# INTERFACE.net
KiCad netlist of a schematic drawn in Altium Designer
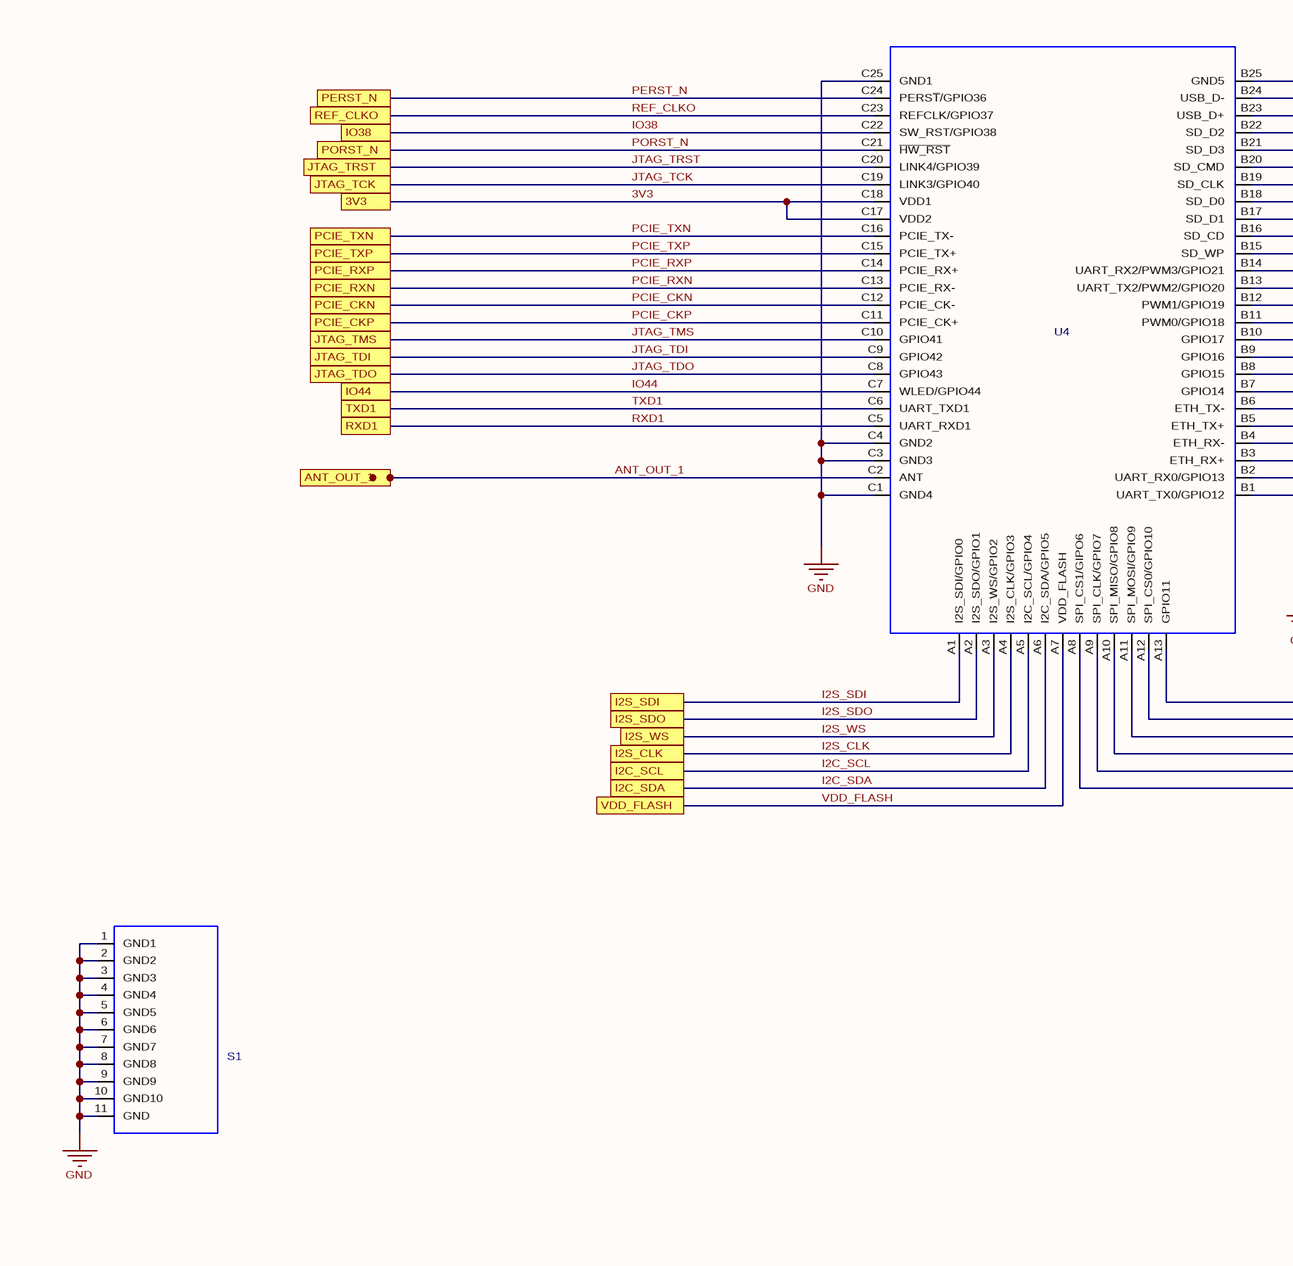
[diagram p0: INTERFACE.SchDoc, left]
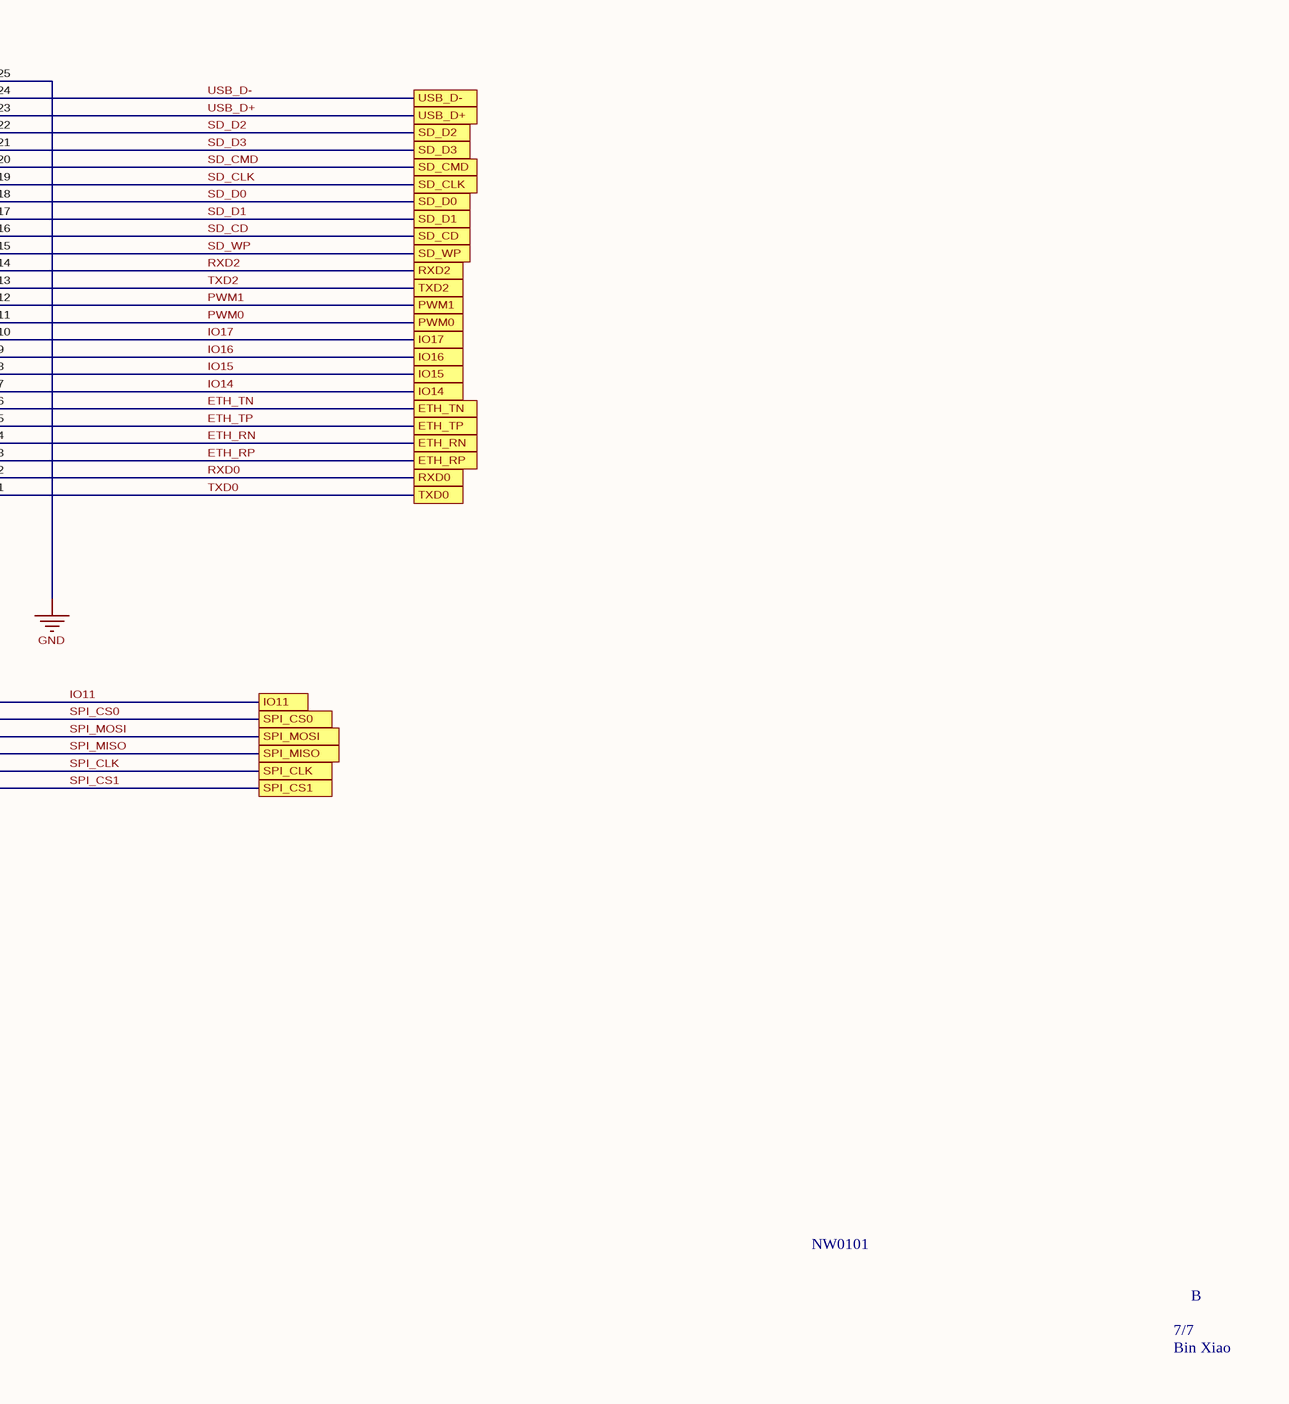
[diagram p1: INTERFACE.SchDoc, right]

(export (version "E")
  (design (tool "Eeschema 10.0.6"))
  (components
    (comp (ref "S1")
      (value "O2S-SHIELD")
      (footprint "O2S-SHIELD")
      (description "O2S SHIELD")
      (fields (field (name "MANUFACTURER") "RYSE Inc."))
      (libsource (lib "*") (part "O2S-SHIELD"))
    )
    (comp (ref "U4")
      (value "OMEGA2S-PCB")
      (footprint "OMEGA2S+PCB")
      (description "RX TXRX MODULE WIFI U.FL SMD")
      (fields (field (name "MANUFACTURER") "Onion Corporation") (field (name "PART NUMBER") "OM-O2S"))
      (libsource (lib "*") (part "OMEGA2S-PCB"))
    )
  )
  (nets
    (net (code "1") (name "/3V3") (class "Default")
      (node (ref "U4") (pin "C17") (pinfunction "VDD2_C17") (pintype "passive"))
      (node (ref "U4") (pin "C18") (pinfunction "VDD1_C18") (pintype "passive"))
    )
    (net (code "2") (name "/ANT_OUT_1") (class "Default")
      (node (ref "U4") (pin "C2") (pinfunction "ANT_C2") (pintype "passive"))
    )
    (net (code "3") (name "/ETH_RN") (class "Default")
      (node (ref "U4") (pin "B4") (pinfunction "ETH_RX-_B4") (pintype "passive"))
    )
    (net (code "4") (name "/ETH_RP") (class "Default")
      (node (ref "U4") (pin "B3") (pinfunction "ETH_RX+_B3") (pintype "passive"))
    )
    (net (code "5") (name "/ETH_TN") (class "Default")
      (node (ref "U4") (pin "B6") (pinfunction "ETH_TX-_B6") (pintype "passive"))
    )
    (net (code "6") (name "/ETH_TP") (class "Default")
      (node (ref "U4") (pin "B5") (pinfunction "ETH_TX+_B5") (pintype "passive"))
    )
    (net (code "7") (name "/I2C_SCL") (class "Default")
      (node (ref "U4") (pin "A5") (pinfunction "I2C_SCL/GPIO4_A5") (pintype "passive"))
    )
    (net (code "8") (name "/I2C_SDA") (class "Default")
      (node (ref "U4") (pin "A6") (pinfunction "I2C_SDA/GPIO5_A6") (pintype "passive"))
    )
    (net (code "9") (name "/I2S_CLK") (class "Default")
      (node (ref "U4") (pin "A4") (pinfunction "I2S_CLK/GPIO3_A4") (pintype "passive"))
    )
    (net (code "10") (name "/I2S_SDI") (class "Default")
      (node (ref "U4") (pin "A1") (pinfunction "I2S_SDI/GPIO0_A1") (pintype "passive"))
    )
    (net (code "11") (name "/I2S_SDO") (class "Default")
      (node (ref "U4") (pin "A2") (pinfunction "I2S_SDO/GPIO1_A2") (pintype "passive"))
    )
    (net (code "12") (name "/I2S_WS") (class "Default")
      (node (ref "U4") (pin "A3") (pinfunction "I2S_WS/GPIO2_A3") (pintype "passive"))
    )
    (net (code "13") (name "/IO11") (class "Default")
      (node (ref "U4") (pin "A13") (pinfunction "GPIO11_A13") (pintype "passive"))
    )
    (net (code "14") (name "/IO14") (class "Default")
      (node (ref "U4") (pin "B7") (pinfunction "GPIO14_B7") (pintype "passive"))
    )
    (net (code "15") (name "/IO15") (class "Default")
      (node (ref "U4") (pin "B8") (pinfunction "GPIO15_B8") (pintype "passive"))
    )
    (net (code "16") (name "/IO16") (class "Default")
      (node (ref "U4") (pin "B9") (pinfunction "GPIO16_B9") (pintype "passive"))
    )
    (net (code "17") (name "/IO17") (class "Default")
      (node (ref "U4") (pin "B10") (pinfunction "GPIO17_B10") (pintype "passive"))
    )
    (net (code "18") (name "/IO38") (class "Default")
      (node (ref "U4") (pin "C22") (pinfunction "SW_RST/GPIO38_C22") (pintype "passive"))
    )
    (net (code "19") (name "/IO44") (class "Default")
      (node (ref "U4") (pin "C7") (pinfunction "WLED/GPIO44_C7") (pintype "passive"))
    )
    (net (code "20") (name "/JTAG_TCK") (class "Default")
      (node (ref "U4") (pin "C19") (pinfunction "LINK3/GPIO40_C19") (pintype "passive"))
    )
    (net (code "21") (name "/JTAG_TDI") (class "Default")
      (node (ref "U4") (pin "C9") (pinfunction "GPIO42_C9") (pintype "passive"))
    )
    (net (code "22") (name "/JTAG_TDO") (class "Default")
      (node (ref "U4") (pin "C8") (pinfunction "GPIO43_C8") (pintype "passive"))
    )
    (net (code "23") (name "/JTAG_TMS") (class "Default")
      (node (ref "U4") (pin "C10") (pinfunction "GPIO41_C10") (pintype "passive"))
    )
    (net (code "24") (name "/JTAG_TRST") (class "Default")
      (node (ref "U4") (pin "C20") (pinfunction "LINK4/GPIO39_C20") (pintype "passive"))
    )
    (net (code "25") (name "/PCIE_CKN") (class "Default")
      (node (ref "U4") (pin "C12") (pinfunction "PCIE_CK-_C12") (pintype "passive"))
    )
    (net (code "26") (name "/PCIE_CKP") (class "Default")
      (node (ref "U4") (pin "C11") (pinfunction "PCIE_CK+_C11") (pintype "passive"))
    )
    (net (code "27") (name "/PCIE_RXN") (class "Default")
      (node (ref "U4") (pin "C13") (pinfunction "PCIE_RX-_C13") (pintype "passive"))
    )
    (net (code "28") (name "/PCIE_RXP") (class "Default")
      (node (ref "U4") (pin "C14") (pinfunction "PCIE_RX+_C14") (pintype "passive"))
    )
    (net (code "29") (name "/PCIE_TXN") (class "Default")
      (node (ref "U4") (pin "C16") (pinfunction "PCIE_TX-_C16") (pintype "passive"))
    )
    (net (code "30") (name "/PCIE_TXP") (class "Default")
      (node (ref "U4") (pin "C15") (pinfunction "PCIE_TX+_C15") (pintype "passive"))
    )
    (net (code "31") (name "/PERST_N") (class "Default")
      (node (ref "U4") (pin "C24") (pinfunction "PERS~{T}/GPIO36_C24") (pintype "passive"))
    )
    (net (code "32") (name "/PORST_N") (class "Default")
      (node (ref "U4") (pin "C21") (pinfunction "HW_RST_C21") (pintype "passive"))
    )
    (net (code "33") (name "/PWM0") (class "Default")
      (node (ref "U4") (pin "B11") (pinfunction "PWM0/GPIO18_B11") (pintype "passive"))
    )
    (net (code "34") (name "/PWM1") (class "Default")
      (node (ref "U4") (pin "B12") (pinfunction "PWM1/GPIO19_B12") (pintype "passive"))
    )
    (net (code "35") (name "/REF_CLKO") (class "Default")
      (node (ref "U4") (pin "C23") (pinfunction "REFCLK/GPIO37_C23") (pintype "passive"))
    )
    (net (code "36") (name "/RXD0") (class "Default")
      (node (ref "U4") (pin "B2") (pinfunction "UART_RX0/GPIO13_B2") (pintype "passive"))
    )
    (net (code "37") (name "/RXD1") (class "Default")
      (node (ref "U4") (pin "C5") (pinfunction "UART_RXD1_C5") (pintype "passive"))
    )
    (net (code "38") (name "/RXD2") (class "Default")
      (node (ref "U4") (pin "B14") (pinfunction "UART_RX2/PWM3/GPIO21_B14") (pintype "passive"))
    )
    (net (code "39") (name "/SD_CD") (class "Default")
      (node (ref "U4") (pin "B16") (pinfunction "SD_CD_B16") (pintype "passive"))
    )
    (net (code "40") (name "/SD_CLK") (class "Default")
      (node (ref "U4") (pin "B19") (pinfunction "SD_CLK_B19") (pintype "passive"))
    )
    (net (code "41") (name "/SD_CMD") (class "Default")
      (node (ref "U4") (pin "B20") (pinfunction "SD_CMD_B20") (pintype "passive"))
    )
    (net (code "42") (name "/SD_D0") (class "Default")
      (node (ref "U4") (pin "B18") (pinfunction "SD_D0_B18") (pintype "passive"))
    )
    (net (code "43") (name "/SD_D1") (class "Default")
      (node (ref "U4") (pin "B17") (pinfunction "SD_D1_B17") (pintype "passive"))
    )
    (net (code "44") (name "/SD_D2") (class "Default")
      (node (ref "U4") (pin "B22") (pinfunction "SD_D2_B22") (pintype "passive"))
    )
    (net (code "45") (name "/SD_D3") (class "Default")
      (node (ref "U4") (pin "B21") (pinfunction "SD_D3_B21") (pintype "passive"))
    )
    (net (code "46") (name "/SD_WP") (class "Default")
      (node (ref "U4") (pin "B15") (pinfunction "SD_WP_B15") (pintype "passive"))
    )
    (net (code "47") (name "/SPI_CLK") (class "Default")
      (node (ref "U4") (pin "A9") (pinfunction "SPI_CLK/GPIO7_A9") (pintype "passive"))
    )
    (net (code "48") (name "/SPI_CS0") (class "Default")
      (node (ref "U4") (pin "A12") (pinfunction "SPI_CS0/GPIO10_A12") (pintype "passive"))
    )
    (net (code "49") (name "/SPI_CS1") (class "Default")
      (node (ref "U4") (pin "A8") (pinfunction "SPI_CS1/GIPO6_A8") (pintype "passive"))
    )
    (net (code "50") (name "/SPI_MISO") (class "Default")
      (node (ref "U4") (pin "A10") (pinfunction "SPI_MISO/GPIO8_A10") (pintype "passive"))
    )
    (net (code "51") (name "/SPI_MOSI") (class "Default")
      (node (ref "U4") (pin "A11") (pinfunction "SPI_MOSI/GPIO9_A11") (pintype "passive"))
    )
    (net (code "52") (name "/TXD0") (class "Default")
      (node (ref "U4") (pin "B1") (pinfunction "UART_TX0/GPIO12_B1") (pintype "passive"))
    )
    (net (code "53") (name "/TXD1") (class "Default")
      (node (ref "U4") (pin "C6") (pinfunction "UART_TXD1_C6") (pintype "passive"))
    )
    (net (code "54") (name "/TXD2") (class "Default")
      (node (ref "U4") (pin "B13") (pinfunction "UART_TX2/PWM2/GPIO20_B13") (pintype "passive"))
    )
    (net (code "55") (name "/USB_D+") (class "Default")
      (node (ref "U4") (pin "B23") (pinfunction "USB_D+_B23") (pintype "passive"))
    )
    (net (code "56") (name "/USB_D-") (class "Default")
      (node (ref "U4") (pin "B24") (pinfunction "USB_D-_B24") (pintype "passive"))
    )
    (net (code "57") (name "/VDD_FLASH") (class "Default")
      (node (ref "U4") (pin "A7") (pinfunction "VDD_FLASH_A7") (pintype "passive"))
    )
    (net (code "58") (name "GND") (class "Default")
      (node (ref "S1") (pin "1") (pinfunction "GND1_1") (pintype "passive"))
      (node (ref "S1") (pin "10") (pinfunction "GND10_10") (pintype "passive"))
      (node (ref "S1") (pin "11") (pinfunction "GND_11") (pintype "passive"))
      (node (ref "S1") (pin "2") (pinfunction "GND2_2") (pintype "passive"))
      (node (ref "S1") (pin "3") (pinfunction "GND3_3") (pintype "passive"))
      (node (ref "S1") (pin "4") (pinfunction "GND4_4") (pintype "passive"))
      (node (ref "S1") (pin "5") (pinfunction "GND5_5") (pintype "passive"))
      (node (ref "S1") (pin "6") (pinfunction "GND6_6") (pintype "passive"))
      (node (ref "S1") (pin "7") (pinfunction "GND7_7") (pintype "passive"))
      (node (ref "S1") (pin "8") (pinfunction "GND8_8") (pintype "passive"))
      (node (ref "S1") (pin "9") (pinfunction "GND9_9") (pintype "passive"))
      (node (ref "U4") (pin "B25") (pinfunction "GND5_B25") (pintype "passive"))
      (node (ref "U4") (pin "C1") (pinfunction "GND4_C1") (pintype "passive"))
      (node (ref "U4") (pin "C25") (pinfunction "GND1_C25") (pintype "passive"))
      (node (ref "U4") (pin "C3") (pinfunction "GND3_C3") (pintype "passive"))
      (node (ref "U4") (pin "C4") (pinfunction "GND2_C4") (pintype "passive"))
    )
  )
)
